# CompleteBoard.net
KiCad netlist of a schematic drawn in EAGLE
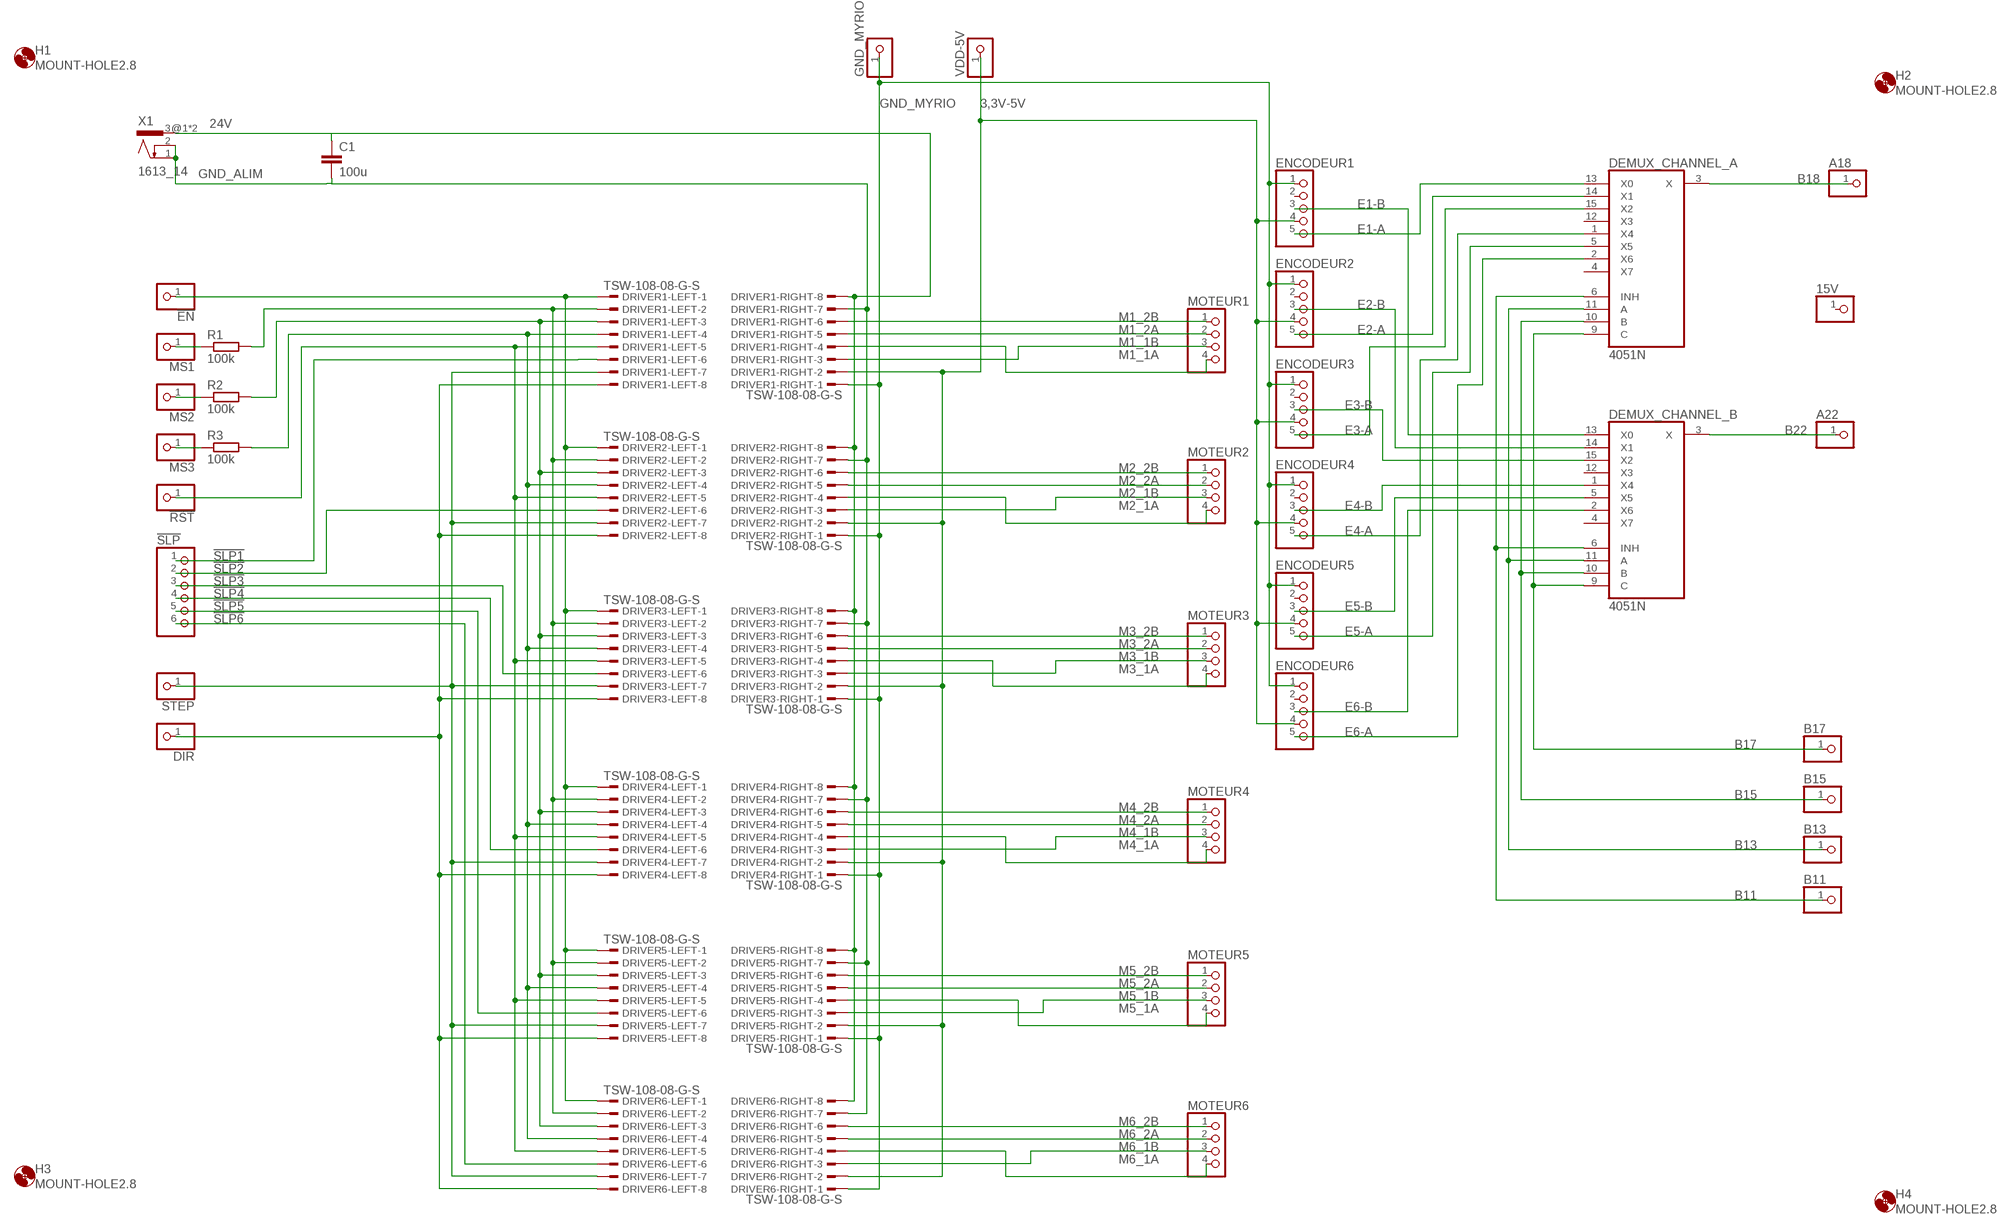
[diagram p0: schematic, sheet 1]

(export (version "E")
  (design (tool "Eeschema 10.0.6"))
  (components
    (comp (ref "!EN")
      (value "PINHD-1X1")
      (footprint "eagle-import:1X01")
      (libsource (lib "eagle-import") (part "PINHD-1X1"))
    )
    (comp (ref "!RST")
      (value "PINHD-1X1")
      (footprint "eagle-import:1X01")
      (libsource (lib "eagle-import") (part "PINHD-1X1"))
    )
    (comp (ref "!SLP")
      (value "PINHD-1X6")
      (footprint "eagle-import:1X06")
      (libsource (lib "eagle-import") (part "PINHD-1X6"))
    )
    (comp (ref "15V")
      (value "PINHD-1X1")
      (footprint "eagle-import:1X01")
      (libsource (lib "eagle-import") (part "PINHD-1X1"))
    )
    (comp (ref "A18")
      (value "PINHD-1X1")
      (footprint "eagle-import:1X01")
      (libsource (lib "eagle-import") (part "PINHD-1X1"))
    )
    (comp (ref "A22")
      (value "PINHD-1X1")
      (footprint "eagle-import:1X01")
      (libsource (lib "eagle-import") (part "PINHD-1X1"))
    )
    (comp (ref "B11")
      (value "PINHD-1X1")
      (footprint "eagle-import:1X01")
      (libsource (lib "eagle-import") (part "PINHD-1X1"))
    )
    (comp (ref "B13")
      (value "PINHD-1X1")
      (footprint "eagle-import:1X01")
      (libsource (lib "eagle-import") (part "PINHD-1X1"))
    )
    (comp (ref "B15")
      (value "PINHD-1X1")
      (footprint "eagle-import:1X01")
      (libsource (lib "eagle-import") (part "PINHD-1X1"))
    )
    (comp (ref "B17")
      (value "PINHD-1X1")
      (footprint "eagle-import:1X01")
      (libsource (lib "eagle-import") (part "PINHD-1X1"))
    )
    (comp (ref "C1")
      (value "100u")
      (footprint "eagle-import:C025-025X050")
      (libsource (lib "eagle-import") (part "C-EU025-025X050"))
    )
    (comp (ref "DEMUX_CHANNEL_A")
      (value "4051N")
      (footprint "eagle-import:DIL16")
      (libsource (lib "eagle-import") (part "4051N"))
    )
    (comp (ref "DEMUX_CHANNEL_B")
      (value "4051N")
      (footprint "eagle-import:DIL16")
      (libsource (lib "eagle-import") (part "4051N"))
    )
    (comp (ref "DIR")
      (value "PINHD-1X1")
      (footprint "eagle-import:1X01")
      (libsource (lib "eagle-import") (part "PINHD-1X1"))
    )
    (comp (ref "DRIVER1-LEFT")
      (value "TSW-108-08-G-S")
      (footprint "eagle-import:TSW-108-XX-G-S")
      (fields (field (name "MF") "Samtec Inc.") (field (name "MPN") "TSW-108-07-G-S"))
      (libsource (lib "eagle-import") (part "TSW-108--G-S08"))
    )
    (comp (ref "DRIVER1-RIGHT")
      (value "TSW-108-08-G-S")
      (footprint "eagle-import:TSW-108-XX-G-S")
      (fields (field (name "MF") "Samtec Inc.") (field (name "MPN") "TSW-108-07-G-S"))
      (libsource (lib "eagle-import") (part "TSW-108--G-S08"))
    )
    (comp (ref "DRIVER2-LEFT")
      (value "TSW-108-08-G-S")
      (footprint "eagle-import:TSW-108-XX-G-S")
      (fields (field (name "MF") "Samtec Inc.") (field (name "MPN") "TSW-108-07-G-S"))
      (libsource (lib "eagle-import") (part "TSW-108--G-S08"))
    )
    (comp (ref "DRIVER2-RIGHT")
      (value "TSW-108-08-G-S")
      (footprint "eagle-import:TSW-108-XX-G-S")
      (fields (field (name "MF") "Samtec Inc.") (field (name "MPN") "TSW-108-07-G-S"))
      (libsource (lib "eagle-import") (part "TSW-108--G-S08"))
    )
    (comp (ref "DRIVER3-LEFT")
      (value "TSW-108-08-G-S")
      (footprint "eagle-import:TSW-108-XX-G-S")
      (fields (field (name "MF") "Samtec Inc.") (field (name "MPN") "TSW-108-07-G-S"))
      (libsource (lib "eagle-import") (part "TSW-108--G-S08"))
    )
    (comp (ref "DRIVER3-RIGHT")
      (value "TSW-108-08-G-S")
      (footprint "eagle-import:TSW-108-XX-G-S")
      (fields (field (name "MF") "Samtec Inc.") (field (name "MPN") "TSW-108-07-G-S"))
      (libsource (lib "eagle-import") (part "TSW-108--G-S08"))
    )
    (comp (ref "DRIVER4-LEFT")
      (value "TSW-108-08-G-S")
      (footprint "eagle-import:TSW-108-XX-G-S")
      (fields (field (name "MF") "Samtec Inc.") (field (name "MPN") "TSW-108-07-G-S"))
      (libsource (lib "eagle-import") (part "TSW-108--G-S08"))
    )
    (comp (ref "DRIVER4-RIGHT")
      (value "TSW-108-08-G-S")
      (footprint "eagle-import:TSW-108-XX-G-S")
      (fields (field (name "MF") "Samtec Inc.") (field (name "MPN") "TSW-108-07-G-S"))
      (libsource (lib "eagle-import") (part "TSW-108--G-S08"))
    )
    (comp (ref "DRIVER5-LEFT")
      (value "TSW-108-08-G-S")
      (footprint "eagle-import:TSW-108-XX-G-S")
      (fields (field (name "MF") "Samtec Inc.") (field (name "MPN") "TSW-108-07-G-S"))
      (libsource (lib "eagle-import") (part "TSW-108--G-S08"))
    )
    (comp (ref "DRIVER5-RIGHT")
      (value "TSW-108-08-G-S")
      (footprint "eagle-import:TSW-108-XX-G-S")
      (fields (field (name "MF") "Samtec Inc.") (field (name "MPN") "TSW-108-07-G-S"))
      (libsource (lib "eagle-import") (part "TSW-108--G-S08"))
    )
    (comp (ref "DRIVER6-LEFT")
      (value "TSW-108-08-G-S")
      (footprint "eagle-import:TSW-108-XX-G-S")
      (fields (field (name "MF") "Samtec Inc.") (field (name "MPN") "TSW-108-07-G-S"))
      (libsource (lib "eagle-import") (part "TSW-108--G-S08"))
    )
    (comp (ref "DRIVER6-RIGHT")
      (value "TSW-108-08-G-S")
      (footprint "eagle-import:TSW-108-XX-G-S")
      (fields (field (name "MF") "Samtec Inc.") (field (name "MPN") "TSW-108-07-G-S"))
      (libsource (lib "eagle-import") (part "TSW-108--G-S08"))
    )
    (comp (ref "ENCODEUR1")
      (value "PINHD-1X5")
      (footprint "eagle-import:1X05")
      (libsource (lib "eagle-import") (part "PINHD-1X5"))
    )
    (comp (ref "ENCODEUR2")
      (value "PINHD-1X5")
      (footprint "eagle-import:1X05")
      (libsource (lib "eagle-import") (part "PINHD-1X5"))
    )
    (comp (ref "ENCODEUR3")
      (value "PINHD-1X5")
      (footprint "eagle-import:1X05")
      (libsource (lib "eagle-import") (part "PINHD-1X5"))
    )
    (comp (ref "ENCODEUR4")
      (value "PINHD-1X5")
      (footprint "eagle-import:1X05")
      (libsource (lib "eagle-import") (part "PINHD-1X5"))
    )
    (comp (ref "ENCODEUR5")
      (value "PINHD-1X5")
      (footprint "eagle-import:1X05")
      (libsource (lib "eagle-import") (part "PINHD-1X5"))
    )
    (comp (ref "ENCODEUR6")
      (value "PINHD-1X5")
      (footprint "eagle-import:1X05")
      (libsource (lib "eagle-import") (part "PINHD-1X5"))
    )
    (comp (ref "GND_MYRIO")
      (value "PINHD-1X1")
      (footprint "eagle-import:1X01")
      (libsource (lib "eagle-import") (part "PINHD-1X1"))
    )
    (comp (ref "H1")
      (value "MOUNT-HOLE2.8")
      (footprint "eagle-import:2,8")
      (libsource (lib "eagle-import") (part "MOUNT-HOLE2.8"))
    )
    (comp (ref "H2")
      (value "MOUNT-HOLE2.8")
      (footprint "eagle-import:2,8")
      (libsource (lib "eagle-import") (part "MOUNT-HOLE2.8"))
    )
    (comp (ref "H3")
      (value "MOUNT-HOLE2.8")
      (footprint "eagle-import:2,8")
      (libsource (lib "eagle-import") (part "MOUNT-HOLE2.8"))
    )
    (comp (ref "H4")
      (value "MOUNT-HOLE2.8")
      (footprint "eagle-import:2,8")
      (libsource (lib "eagle-import") (part "MOUNT-HOLE2.8"))
    )
    (comp (ref "MOTEUR1")
      (value "PINHD-1X4")
      (footprint "eagle-import:1X04")
      (libsource (lib "eagle-import") (part "PINHD-1X4"))
    )
    (comp (ref "MOTEUR2")
      (value "PINHD-1X4")
      (footprint "eagle-import:1X04")
      (libsource (lib "eagle-import") (part "PINHD-1X4"))
    )
    (comp (ref "MOTEUR3")
      (value "PINHD-1X4")
      (footprint "eagle-import:1X04")
      (libsource (lib "eagle-import") (part "PINHD-1X4"))
    )
    (comp (ref "MOTEUR4")
      (value "PINHD-1X4")
      (footprint "eagle-import:1X04")
      (libsource (lib "eagle-import") (part "PINHD-1X4"))
    )
    (comp (ref "MOTEUR5")
      (value "PINHD-1X4")
      (footprint "eagle-import:1X04")
      (libsource (lib "eagle-import") (part "PINHD-1X4"))
    )
    (comp (ref "MOTEUR6")
      (value "PINHD-1X4")
      (footprint "eagle-import:1X04")
      (libsource (lib "eagle-import") (part "PINHD-1X4"))
    )
    (comp (ref "MS1")
      (value "PINHD-1X1")
      (footprint "eagle-import:1X01")
      (libsource (lib "eagle-import") (part "PINHD-1X1"))
    )
    (comp (ref "MS2")
      (value "PINHD-1X1")
      (footprint "eagle-import:1X01")
      (libsource (lib "eagle-import") (part "PINHD-1X1"))
    )
    (comp (ref "MS3")
      (value "PINHD-1X1")
      (footprint "eagle-import:1X01")
      (libsource (lib "eagle-import") (part "PINHD-1X1"))
    )
    (comp (ref "R1")
      (value "100k")
      (footprint "eagle-import:0204_7")
      (libsource (lib "eagle-import") (part "R-EU_0204/7"))
    )
    (comp (ref "R2")
      (value "100k")
      (footprint "eagle-import:0204_7")
      (libsource (lib "eagle-import") (part "R-EU_0204/7"))
    )
    (comp (ref "R3")
      (value "100k")
      (footprint "eagle-import:0204_7")
      (libsource (lib "eagle-import") (part "R-EU_0204/7"))
    )
    (comp (ref "STEP")
      (value "PINHD-1X1")
      (footprint "eagle-import:1X01")
      (libsource (lib "eagle-import") (part "PINHD-1X1"))
    )
    (comp (ref "VDD-5V")
      (value "PINHD-1X1")
      (footprint "eagle-import:1X01")
      (libsource (lib "eagle-import") (part "PINHD-1X1"))
    )
    (comp (ref "X1")
      (value "1613_14")
      (footprint "eagle-import:1613_14")
      (fields (field (name "MF") "LUMBERG") (field (name "MPN") "1613 14"))
      (libsource (lib "eagle-import") (part "1613_14"))
    )
  )
  (nets
    (net (code "1") (name "/3,3V-5V") (class "Default")
      (node (ref "DRIVER1-RIGHT") (pin "2") (pinfunction "1_2") (pintype "passive"))
      (node (ref "DRIVER2-RIGHT") (pin "2") (pinfunction "1_2") (pintype "passive"))
      (node (ref "DRIVER3-RIGHT") (pin "2") (pinfunction "1_2") (pintype "passive"))
      (node (ref "DRIVER4-RIGHT") (pin "2") (pinfunction "1_2") (pintype "passive"))
      (node (ref "DRIVER5-RIGHT") (pin "2") (pinfunction "1_2") (pintype "passive"))
      (node (ref "DRIVER6-RIGHT") (pin "2") (pinfunction "1_2") (pintype "passive"))
      (node (ref "ENCODEUR1") (pin "4") (pinfunction "4_4") (pintype "passive"))
      (node (ref "ENCODEUR2") (pin "4") (pinfunction "4_4") (pintype "passive"))
      (node (ref "ENCODEUR3") (pin "4") (pinfunction "4_4") (pintype "passive"))
      (node (ref "ENCODEUR4") (pin "4") (pinfunction "4_4") (pintype "passive"))
      (node (ref "ENCODEUR5") (pin "4") (pinfunction "4_4") (pintype "passive"))
      (node (ref "ENCODEUR6") (pin "4") (pinfunction "4_4") (pintype "passive"))
      (node (ref "VDD-5V") (pin "1") (pinfunction "1_1") (pintype "passive"))
    )
    (net (code "2") (name "/24V") (class "Default")
      (node (ref "C1") (pin "1") (pinfunction "1_1") (pintype "passive"))
      (node (ref "DRIVER1-RIGHT") (pin "8") (pinfunction "1_8") (pintype "passive"))
      (node (ref "DRIVER2-RIGHT") (pin "8") (pinfunction "1_8") (pintype "passive"))
      (node (ref "DRIVER3-RIGHT") (pin "8") (pinfunction "1_8") (pintype "passive"))
      (node (ref "DRIVER4-RIGHT") (pin "8") (pinfunction "1_8") (pintype "passive"))
      (node (ref "DRIVER5-RIGHT") (pin "8") (pinfunction "1_8") (pintype "passive"))
      (node (ref "DRIVER6-RIGHT") (pin "8") (pinfunction "1_8") (pintype "passive"))
      (node (ref "X1") (pin "3@1") (pinfunction "3_3@1") (pintype "passive"))
      (node (ref "X1") (pin "3@2") (pinfunction "3_3@2") (pintype "passive"))
    )
    (net (code "3") (name "/B11") (class "Default")
      (node (ref "B11") (pin "1") (pinfunction "1_1") (pintype "passive"))
      (node (ref "DEMUX_CHANNEL_A") (pin "6") (pinfunction "INH_6") (pintype "input"))
      (node (ref "DEMUX_CHANNEL_B") (pin "6") (pinfunction "INH_6") (pintype "input"))
    )
    (net (code "4") (name "/B13") (class "Default")
      (node (ref "B13") (pin "1") (pinfunction "1_1") (pintype "passive"))
      (node (ref "DEMUX_CHANNEL_A") (pin "11") (pinfunction "A_11") (pintype "input"))
      (node (ref "DEMUX_CHANNEL_B") (pin "11") (pinfunction "A_11") (pintype "input"))
    )
    (net (code "5") (name "/B15") (class "Default")
      (node (ref "B15") (pin "1") (pinfunction "1_1") (pintype "passive"))
      (node (ref "DEMUX_CHANNEL_A") (pin "10") (pinfunction "B_10") (pintype "input"))
      (node (ref "DEMUX_CHANNEL_B") (pin "10") (pinfunction "B_10") (pintype "input"))
    )
    (net (code "6") (name "/B17") (class "Default")
      (node (ref "B17") (pin "1") (pinfunction "1_1") (pintype "passive"))
      (node (ref "DEMUX_CHANNEL_A") (pin "9") (pinfunction "C_9") (pintype "input"))
      (node (ref "DEMUX_CHANNEL_B") (pin "9") (pinfunction "C_9") (pintype "input"))
    )
    (net (code "7") (name "/B18") (class "Default")
      (node (ref "A18") (pin "1") (pinfunction "1_1") (pintype "passive"))
      (node (ref "DEMUX_CHANNEL_A") (pin "3") (pinfunction "X_3") (pintype "bidirectional"))
    )
    (net (code "8") (name "/B22") (class "Default")
      (node (ref "A22") (pin "1") (pinfunction "1_1") (pintype "passive"))
      (node (ref "DEMUX_CHANNEL_B") (pin "3") (pinfunction "X_3") (pintype "bidirectional"))
    )
    (net (code "9") (name "/E1-A") (class "Default")
      (node (ref "DEMUX_CHANNEL_A") (pin "13") (pinfunction "X0_13") (pintype "bidirectional"))
      (node (ref "ENCODEUR1") (pin "5") (pinfunction "5_5") (pintype "passive"))
    )
    (net (code "10") (name "/E1-B") (class "Default")
      (node (ref "DEMUX_CHANNEL_B") (pin "13") (pinfunction "X0_13") (pintype "bidirectional"))
      (node (ref "ENCODEUR1") (pin "3") (pinfunction "3_3") (pintype "passive"))
    )
    (net (code "11") (name "/E2-A") (class "Default")
      (node (ref "DEMUX_CHANNEL_A") (pin "14") (pinfunction "X1_14") (pintype "bidirectional"))
      (node (ref "ENCODEUR2") (pin "5") (pinfunction "5_5") (pintype "passive"))
    )
    (net (code "12") (name "/E2-B") (class "Default")
      (node (ref "DEMUX_CHANNEL_B") (pin "14") (pinfunction "X1_14") (pintype "bidirectional"))
      (node (ref "ENCODEUR2") (pin "3") (pinfunction "3_3") (pintype "passive"))
    )
    (net (code "13") (name "/E3-A") (class "Default")
      (node (ref "DEMUX_CHANNEL_A") (pin "15") (pinfunction "X2_15") (pintype "bidirectional"))
      (node (ref "ENCODEUR3") (pin "5") (pinfunction "5_5") (pintype "passive"))
    )
    (net (code "14") (name "/E3-B") (class "Default")
      (node (ref "DEMUX_CHANNEL_B") (pin "15") (pinfunction "X2_15") (pintype "bidirectional"))
      (node (ref "ENCODEUR3") (pin "3") (pinfunction "3_3") (pintype "passive"))
    )
    (net (code "15") (name "/E4-A") (class "Default")
      (node (ref "DEMUX_CHANNEL_A") (pin "1") (pinfunction "X4_1") (pintype "bidirectional"))
      (node (ref "ENCODEUR4") (pin "5") (pinfunction "5_5") (pintype "passive"))
    )
    (net (code "16") (name "/E4-B") (class "Default")
      (node (ref "DEMUX_CHANNEL_B") (pin "1") (pinfunction "X4_1") (pintype "bidirectional"))
      (node (ref "ENCODEUR4") (pin "3") (pinfunction "3_3") (pintype "passive"))
    )
    (net (code "17") (name "/E5-A") (class "Default")
      (node (ref "DEMUX_CHANNEL_A") (pin "5") (pinfunction "X5_5") (pintype "bidirectional"))
      (node (ref "ENCODEUR5") (pin "5") (pinfunction "5_5") (pintype "passive"))
    )
    (net (code "18") (name "/E5-B") (class "Default")
      (node (ref "DEMUX_CHANNEL_B") (pin "5") (pinfunction "X5_5") (pintype "bidirectional"))
      (node (ref "ENCODEUR5") (pin "3") (pinfunction "3_3") (pintype "passive"))
    )
    (net (code "19") (name "/E6-A") (class "Default")
      (node (ref "DEMUX_CHANNEL_A") (pin "2") (pinfunction "X6_2") (pintype "bidirectional"))
      (node (ref "ENCODEUR6") (pin "5") (pinfunction "5_5") (pintype "passive"))
    )
    (net (code "20") (name "/E6-B") (class "Default")
      (node (ref "DEMUX_CHANNEL_B") (pin "2") (pinfunction "X6_2") (pintype "bidirectional"))
      (node (ref "ENCODEUR6") (pin "3") (pinfunction "3_3") (pintype "passive"))
    )
    (net (code "21") (name "/GND_ALIM") (class "Default")
      (node (ref "C1") (pin "2") (pinfunction "2_2") (pintype "passive"))
      (node (ref "DRIVER1-RIGHT") (pin "7") (pinfunction "1_7") (pintype "passive"))
      (node (ref "DRIVER2-RIGHT") (pin "7") (pinfunction "1_7") (pintype "passive"))
      (node (ref "DRIVER3-RIGHT") (pin "7") (pinfunction "1_7") (pintype "passive"))
      (node (ref "DRIVER4-RIGHT") (pin "7") (pinfunction "1_7") (pintype "passive"))
      (node (ref "DRIVER5-RIGHT") (pin "7") (pinfunction "1_7") (pintype "passive"))
      (node (ref "DRIVER6-RIGHT") (pin "7") (pinfunction "1_7") (pintype "passive"))
      (node (ref "X1") (pin "1") (pinfunction "1_1") (pintype "passive"))
      (node (ref "X1") (pin "2") (pinfunction "2_2") (pintype "passive"))
    )
    (net (code "22") (name "/GND_MYRIO") (class "Default")
      (node (ref "DRIVER1-RIGHT") (pin "1") (pinfunction "1_1") (pintype "passive"))
      (node (ref "DRIVER2-RIGHT") (pin "1") (pinfunction "1_1") (pintype "passive"))
      (node (ref "DRIVER3-RIGHT") (pin "1") (pinfunction "1_1") (pintype "passive"))
      (node (ref "DRIVER4-RIGHT") (pin "1") (pinfunction "1_1") (pintype "passive"))
      (node (ref "DRIVER5-RIGHT") (pin "1") (pinfunction "1_1") (pintype "passive"))
      (node (ref "DRIVER6-RIGHT") (pin "1") (pinfunction "1_1") (pintype "passive"))
      (node (ref "ENCODEUR1") (pin "1") (pinfunction "1_1") (pintype "passive"))
      (node (ref "ENCODEUR2") (pin "1") (pinfunction "1_1") (pintype "passive"))
      (node (ref "ENCODEUR3") (pin "1") (pinfunction "1_1") (pintype "passive"))
      (node (ref "ENCODEUR4") (pin "1") (pinfunction "1_1") (pintype "passive"))
      (node (ref "ENCODEUR5") (pin "1") (pinfunction "1_1") (pintype "passive"))
      (node (ref "ENCODEUR6") (pin "1") (pinfunction "1_1") (pintype "passive"))
      (node (ref "GND_MYRIO") (pin "1") (pinfunction "1_1") (pintype "passive"))
    )
    (net (code "23") (name "/M1_1A") (class "Default")
      (node (ref "DRIVER1-RIGHT") (pin "4") (pinfunction "1_4") (pintype "passive"))
      (node (ref "MOTEUR1") (pin "4") (pinfunction "4_4") (pintype "passive"))
    )
    (net (code "24") (name "/M1_1B") (class "Default")
      (node (ref "DRIVER1-RIGHT") (pin "3") (pinfunction "1_3") (pintype "passive"))
      (node (ref "MOTEUR1") (pin "3") (pinfunction "3_3") (pintype "passive"))
    )
    (net (code "25") (name "/M1_2A") (class "Default")
      (node (ref "DRIVER1-RIGHT") (pin "5") (pinfunction "1_5") (pintype "passive"))
      (node (ref "MOTEUR1") (pin "2") (pinfunction "2_2") (pintype "passive"))
    )
    (net (code "26") (name "/M1_2B") (class "Default")
      (node (ref "DRIVER1-RIGHT") (pin "6") (pinfunction "1_6") (pintype "passive"))
      (node (ref "MOTEUR1") (pin "1") (pinfunction "1_1") (pintype "passive"))
    )
    (net (code "27") (name "/M2_1A") (class "Default")
      (node (ref "DRIVER2-RIGHT") (pin "4") (pinfunction "1_4") (pintype "passive"))
      (node (ref "MOTEUR2") (pin "4") (pinfunction "4_4") (pintype "passive"))
    )
    (net (code "28") (name "/M2_1B") (class "Default")
      (node (ref "DRIVER2-RIGHT") (pin "3") (pinfunction "1_3") (pintype "passive"))
      (node (ref "MOTEUR2") (pin "3") (pinfunction "3_3") (pintype "passive"))
    )
    (net (code "29") (name "/M2_2A") (class "Default")
      (node (ref "DRIVER2-RIGHT") (pin "5") (pinfunction "1_5") (pintype "passive"))
      (node (ref "MOTEUR2") (pin "2") (pinfunction "2_2") (pintype "passive"))
    )
    (net (code "30") (name "/M2_2B") (class "Default")
      (node (ref "DRIVER2-RIGHT") (pin "6") (pinfunction "1_6") (pintype "passive"))
      (node (ref "MOTEUR2") (pin "1") (pinfunction "1_1") (pintype "passive"))
    )
    (net (code "31") (name "/M3_1A") (class "Default")
      (node (ref "DRIVER3-RIGHT") (pin "4") (pinfunction "1_4") (pintype "passive"))
      (node (ref "MOTEUR3") (pin "4") (pinfunction "4_4") (pintype "passive"))
    )
    (net (code "32") (name "/M3_1B") (class "Default")
      (node (ref "DRIVER3-RIGHT") (pin "3") (pinfunction "1_3") (pintype "passive"))
      (node (ref "MOTEUR3") (pin "3") (pinfunction "3_3") (pintype "passive"))
    )
    (net (code "33") (name "/M3_2A") (class "Default")
      (node (ref "DRIVER3-RIGHT") (pin "5") (pinfunction "1_5") (pintype "passive"))
      (node (ref "MOTEUR3") (pin "2") (pinfunction "2_2") (pintype "passive"))
    )
    (net (code "34") (name "/M3_2B") (class "Default")
      (node (ref "DRIVER3-RIGHT") (pin "6") (pinfunction "1_6") (pintype "passive"))
      (node (ref "MOTEUR3") (pin "1") (pinfunction "1_1") (pintype "passive"))
    )
    (net (code "35") (name "/M4_1A") (class "Default")
      (node (ref "DRIVER4-RIGHT") (pin "4") (pinfunction "1_4") (pintype "passive"))
      (node (ref "MOTEUR4") (pin "4") (pinfunction "4_4") (pintype "passive"))
    )
    (net (code "36") (name "/M4_1B") (class "Default")
      (node (ref "DRIVER4-RIGHT") (pin "3") (pinfunction "1_3") (pintype "passive"))
      (node (ref "MOTEUR4") (pin "3") (pinfunction "3_3") (pintype "passive"))
    )
    (net (code "37") (name "/M4_2A") (class "Default")
      (node (ref "DRIVER4-RIGHT") (pin "5") (pinfunction "1_5") (pintype "passive"))
      (node (ref "MOTEUR4") (pin "2") (pinfunction "2_2") (pintype "passive"))
    )
    (net (code "38") (name "/M4_2B") (class "Default")
      (node (ref "DRIVER4-RIGHT") (pin "6") (pinfunction "1_6") (pintype "passive"))
      (node (ref "MOTEUR4") (pin "1") (pinfunction "1_1") (pintype "passive"))
    )
    (net (code "39") (name "/M5_1A") (class "Default")
      (node (ref "DRIVER5-RIGHT") (pin "4") (pinfunction "1_4") (pintype "passive"))
      (node (ref "MOTEUR5") (pin "4") (pinfunction "4_4") (pintype "passive"))
    )
    (net (code "40") (name "/M5_1B") (class "Default")
      (node (ref "DRIVER5-RIGHT") (pin "3") (pinfunction "1_3") (pintype "passive"))
      (node (ref "MOTEUR5") (pin "3") (pinfunction "3_3") (pintype "passive"))
    )
    (net (code "41") (name "/M5_2A") (class "Default")
      (node (ref "DRIVER5-RIGHT") (pin "5") (pinfunction "1_5") (pintype "passive"))
      (node (ref "MOTEUR5") (pin "2") (pinfunction "2_2") (pintype "passive"))
    )
    (net (code "42") (name "/M5_2B") (class "Default")
      (node (ref "DRIVER5-RIGHT") (pin "6") (pinfunction "1_6") (pintype "passive"))
      (node (ref "MOTEUR5") (pin "1") (pinfunction "1_1") (pintype "passive"))
    )
    (net (code "43") (name "/M6_1A") (class "Default")
      (node (ref "DRIVER6-RIGHT") (pin "4") (pinfunction "1_4") (pintype "passive"))
      (node (ref "MOTEUR6") (pin "4") (pinfunction "4_4") (pintype "passive"))
    )
    (net (code "44") (name "/M6_1B") (class "Default")
      (node (ref "DRIVER6-RIGHT") (pin "3") (pinfunction "1_3") (pintype "passive"))
      (node (ref "MOTEUR6") (pin "3") (pinfunction "3_3") (pintype "passive"))
    )
    (net (code "45") (name "/M6_2A") (class "Default")
      (node (ref "DRIVER6-RIGHT") (pin "5") (pinfunction "1_5") (pintype "passive"))
      (node (ref "MOTEUR6") (pin "2") (pinfunction "2_2") (pintype "passive"))
    )
    (net (code "46") (name "/M6_2B") (class "Default")
      (node (ref "DRIVER6-RIGHT") (pin "6") (pinfunction "1_6") (pintype "passive"))
      (node (ref "MOTEUR6") (pin "1") (pinfunction "1_1") (pintype "passive"))
    )
    (net (code "47") (name "/~{SLP1}") (class "Default")
      (node (ref "!SLP") (pin "1") (pinfunction "1_1") (pintype "passive"))
      (node (ref "DRIVER1-LEFT") (pin "6") (pinfunction "1_6") (pintype "passive"))
    )
    (net (code "48") (name "/~{SLP2}") (class "Default")
      (node (ref "!SLP") (pin "2") (pinfunction "2_2") (pintype "passive"))
      (node (ref "DRIVER2-LEFT") (pin "6") (pinfunction "1_6") (pintype "passive"))
    )
    (net (code "49") (name "/~{SLP3}") (class "Default")
      (node (ref "!SLP") (pin "3") (pinfunction "3_3") (pintype "passive"))
      (node (ref "DRIVER3-LEFT") (pin "6") (pinfunction "1_6") (pintype "passive"))
    )
    (net (code "50") (name "/~{SLP4}") (class "Default")
      (node (ref "!SLP") (pin "4") (pinfunction "4_4") (pintype "passive"))
      (node (ref "DRIVER4-LEFT") (pin "6") (pinfunction "1_6") (pintype "passive"))
    )
    (net (code "51") (name "/~{SLP5}") (class "Default")
      (node (ref "!SLP") (pin "5") (pinfunction "5_5") (pintype "passive"))
      (node (ref "DRIVER5-LEFT") (pin "6") (pinfunction "1_6") (pintype "passive"))
    )
    (net (code "52") (name "/~{SLP6}") (class "Default")
      (node (ref "!SLP") (pin "6") (pinfunction "6_6") (pintype "passive"))
      (node (ref "DRIVER6-LEFT") (pin "6") (pinfunction "1_6") (pintype "passive"))
    )
    (net (code "53") (name "Net-(!EN-Pad1)") (class "Default")
      (node (ref "!EN") (pin "1") (pinfunction "1_1") (pintype "passive"))
      (node (ref "DRIVER1-LEFT") (pin "1") (pinfunction "1_1") (pintype "passive"))
      (node (ref "DRIVER2-LEFT") (pin "1") (pinfunction "1_1") (pintype "passive"))
      (node (ref "DRIVER3-LEFT") (pin "1") (pinfunction "1_1") (pintype "passive"))
      (node (ref "DRIVER4-LEFT") (pin "1") (pinfunction "1_1") (pintype "passive"))
      (node (ref "DRIVER5-LEFT") (pin "1") (pinfunction "1_1") (pintype "passive"))
      (node (ref "DRIVER6-LEFT") (pin "1") (pinfunction "1_1") (pintype "passive"))
    )
    (net (code "54") (name "Net-(DRIVER1-LEFTB-1)") (class "Default")
      (node (ref "DRIVER1-LEFT") (pin "2") (pinfunction "1_2") (pintype "passive"))
      (node (ref "DRIVER2-LEFT") (pin "2") (pinfunction "1_2") (pintype "passive"))
      (node (ref "DRIVER3-LEFT") (pin "2") (pinfunction "1_2") (pintype "passive"))
      (node (ref "DRIVER4-LEFT") (pin "2") (pinfunction "1_2") (pintype "passive"))
      (node (ref "DRIVER5-LEFT") (pin "2") (pinfunction "1_2") (pintype "passive"))
      (node (ref "DRIVER6-LEFT") (pin "2") (pinfunction "1_2") (pintype "passive"))
      (node (ref "R1") (pin "2") (pinfunction "2_2") (pintype "passive"))
    )
    (net (code "55") (name "Net-(DRIVER1-LEFTC-1)") (class "Default")
      (node (ref "DRIVER1-LEFT") (pin "3") (pinfunction "1_3") (pintype "passive"))
      (node (ref "DRIVER2-LEFT") (pin "3") (pinfunction "1_3") (pintype "passive"))
      (node (ref "DRIVER3-LEFT") (pin "3") (pinfunction "1_3") (pintype "passive"))
      (node (ref "DRIVER4-LEFT") (pin "3") (pinfunction "1_3") (pintype "passive"))
      (node (ref "DRIVER5-LEFT") (pin "3") (pinfunction "1_3") (pintype "passive"))
      (node (ref "DRIVER6-LEFT") (pin "3") (pinfunction "1_3") (pintype "passive"))
      (node (ref "R2") (pin "2") (pinfunction "2_2") (pintype "passive"))
    )
    (net (code "56") (name "Net-(DRIVER1-LEFTD-1)") (class "Default")
      (node (ref "DRIVER1-LEFT") (pin "4") (pinfunction "1_4") (pintype "passive"))
      (node (ref "DRIVER2-LEFT") (pin "4") (pinfunction "1_4") (pintype "passive"))
      (node (ref "DRIVER3-LEFT") (pin "4") (pinfunction "1_4") (pintype "passive"))
      (node (ref "DRIVER4-LEFT") (pin "4") (pinfunction "1_4") (pintype "passive"))
      (node (ref "DRIVER5-LEFT") (pin "4") (pinfunction "1_4") (pintype "passive"))
      (node (ref "DRIVER6-LEFT") (pin "4") (pinfunction "1_4") (pintype "passive"))
      (node (ref "R3") (pin "2") (pinfunction "2_2") (pintype "passive"))
    )
    (net (code "57") (name "Net-(DRIVER1-LEFTE-1)") (class "Default")
      (node (ref "!RST") (pin "1") (pinfunction "1_1") (pintype "passive"))
      (node (ref "DRIVER1-LEFT") (pin "5") (pinfunction "1_5") (pintype "passive"))
      (node (ref "DRIVER2-LEFT") (pin "5") (pinfunction "1_5") (pintype "passive"))
      (node (ref "DRIVER3-LEFT") (pin "5") (pinfunction "1_5") (pintype "passive"))
      (node (ref "DRIVER4-LEFT") (pin "5") (pinfunction "1_5") (pintype "passive"))
      (node (ref "DRIVER5-LEFT") (pin "5") (pinfunction "1_5") (pintype "passive"))
      (node (ref "DRIVER6-LEFT") (pin "5") (pinfunction "1_5") (pintype "passive"))
    )
    (net (code "58") (name "Net-(DRIVER1-LEFTG-1)") (class "Default")
      (node (ref "DRIVER1-LEFT") (pin "7") (pinfunction "1_7") (pintype "passive"))
      (node (ref "DRIVER2-LEFT") (pin "7") (pinfunction "1_7") (pintype "passive"))
      (node (ref "DRIVER3-LEFT") (pin "7") (pinfunction "1_7") (pintype "passive"))
      (node (ref "DRIVER4-LEFT") (pin "7") (pinfunction "1_7") (pintype "passive"))
      (node (ref "DRIVER5-LEFT") (pin "7") (pinfunction "1_7") (pintype "passive"))
      (node (ref "DRIVER6-LEFT") (pin "7") (pinfunction "1_7") (pintype "passive"))
      (node (ref "STEP") (pin "1") (pinfunction "1_1") (pintype "passive"))
    )
    (net (code "59") (name "Net-(DRIVER1-LEFTH-1)") (class "Default")
      (node (ref "DIR") (pin "1") (pinfunction "1_1") (pintype "passive"))
      (node (ref "DRIVER1-LEFT") (pin "8") (pinfunction "1_8") (pintype "passive"))
      (node (ref "DRIVER2-LEFT") (pin "8") (pinfunction "1_8") (pintype "passive"))
      (node (ref "DRIVER3-LEFT") (pin "8") (pinfunction "1_8") (pintype "passive"))
      (node (ref "DRIVER4-LEFT") (pin "8") (pinfunction "1_8") (pintype "passive"))
      (node (ref "DRIVER5-LEFT") (pin "8") (pinfunction "1_8") (pintype "passive"))
      (node (ref "DRIVER6-LEFT") (pin "8") (pinfunction "1_8") (pintype "passive"))
    )
    (net (code "60") (name "Net-(MS1-Pad1)") (class "Default")
      (node (ref "MS1") (pin "1") (pinfunction "1_1") (pintype "passive"))
      (node (ref "R1") (pin "1") (pinfunction "1_1") (pintype "passive"))
    )
    (net (code "61") (name "Net-(MS2-Pad1)") (class "Default")
      (node (ref "MS2") (pin "1") (pinfunction "1_1") (pintype "passive"))
      (node (ref "R2") (pin "1") (pinfunction "1_1") (pintype "passive"))
    )
    (net (code "62") (name "Net-(MS3-Pad1)") (class "Default")
      (node (ref "MS3") (pin "1") (pinfunction "1_1") (pintype "passive"))
      (node (ref "R3") (pin "1") (pinfunction "1_1") (pintype "passive"))
    )
    (net (code "63") (name "unconnected-(15V-Pad1)") (class "Default")
      (node (ref "15V") (pin "1") (pinfunction "1_1") (pintype "passive"))
    )
    (net (code "64") (name "unconnected-(DEMUX_CHANNEL_AA-X3-Pad12)") (class "Default")
      (node (ref "DEMUX_CHANNEL_A") (pin "12") (pinfunction "X3_12") (pintype "bidirectional"))
    )
    (net (code "65") (name "unconnected-(DEMUX_CHANNEL_AA-X7-Pad4)") (class "Default")
      (node (ref "DEMUX_CHANNEL_A") (pin "4") (pinfunction "X7_4") (pintype "bidirectional"))
    )
    (net (code "66") (name "unconnected-(DEMUX_CHANNEL_BA-X3-Pad12)") (class "Default")
      (node (ref "DEMUX_CHANNEL_B") (pin "12") (pinfunction "X3_12") (pintype "bidirectional"))
    )
    (net (code "67") (name "unconnected-(DEMUX_CHANNEL_BA-X7-Pad4)") (class "Default")
      (node (ref "DEMUX_CHANNEL_B") (pin "4") (pinfunction "X7_4") (pintype "bidirectional"))
    )
    (net (code "68") (name "unconnected-(ENCODEUR1-Pad2)") (class "Default")
      (node (ref "ENCODEUR1") (pin "2") (pinfunction "2_2") (pintype "passive"))
    )
    (net (code "69") (name "unconnected-(ENCODEUR2-Pad2)") (class "Default")
      (node (ref "ENCODEUR2") (pin "2") (pinfunction "2_2") (pintype "passive"))
    )
    (net (code "70") (name "unconnected-(ENCODEUR3-Pad2)") (class "Default")
      (node (ref "ENCODEUR3") (pin "2") (pinfunction "2_2") (pintype "passive"))
    )
    (net (code "71") (name "unconnected-(ENCODEUR4-Pad2)") (class "Default")
      (node (ref "ENCODEUR4") (pin "2") (pinfunction "2_2") (pintype "passive"))
    )
    (net (code "72") (name "unconnected-(ENCODEUR5-Pad2)") (class "Default")
      (node (ref "ENCODEUR5") (pin "2") (pinfunction "2_2") (pintype "passive"))
    )
    (net (code "73") (name "unconnected-(ENCODEUR6-Pad2)") (class "Default")
      (node (ref "ENCODEUR6") (pin "2") (pinfunction "2_2") (pintype "passive"))
    )
  )
)
